# MAIN.net
KiCad netlist of a schematic drawn in Altium Designer
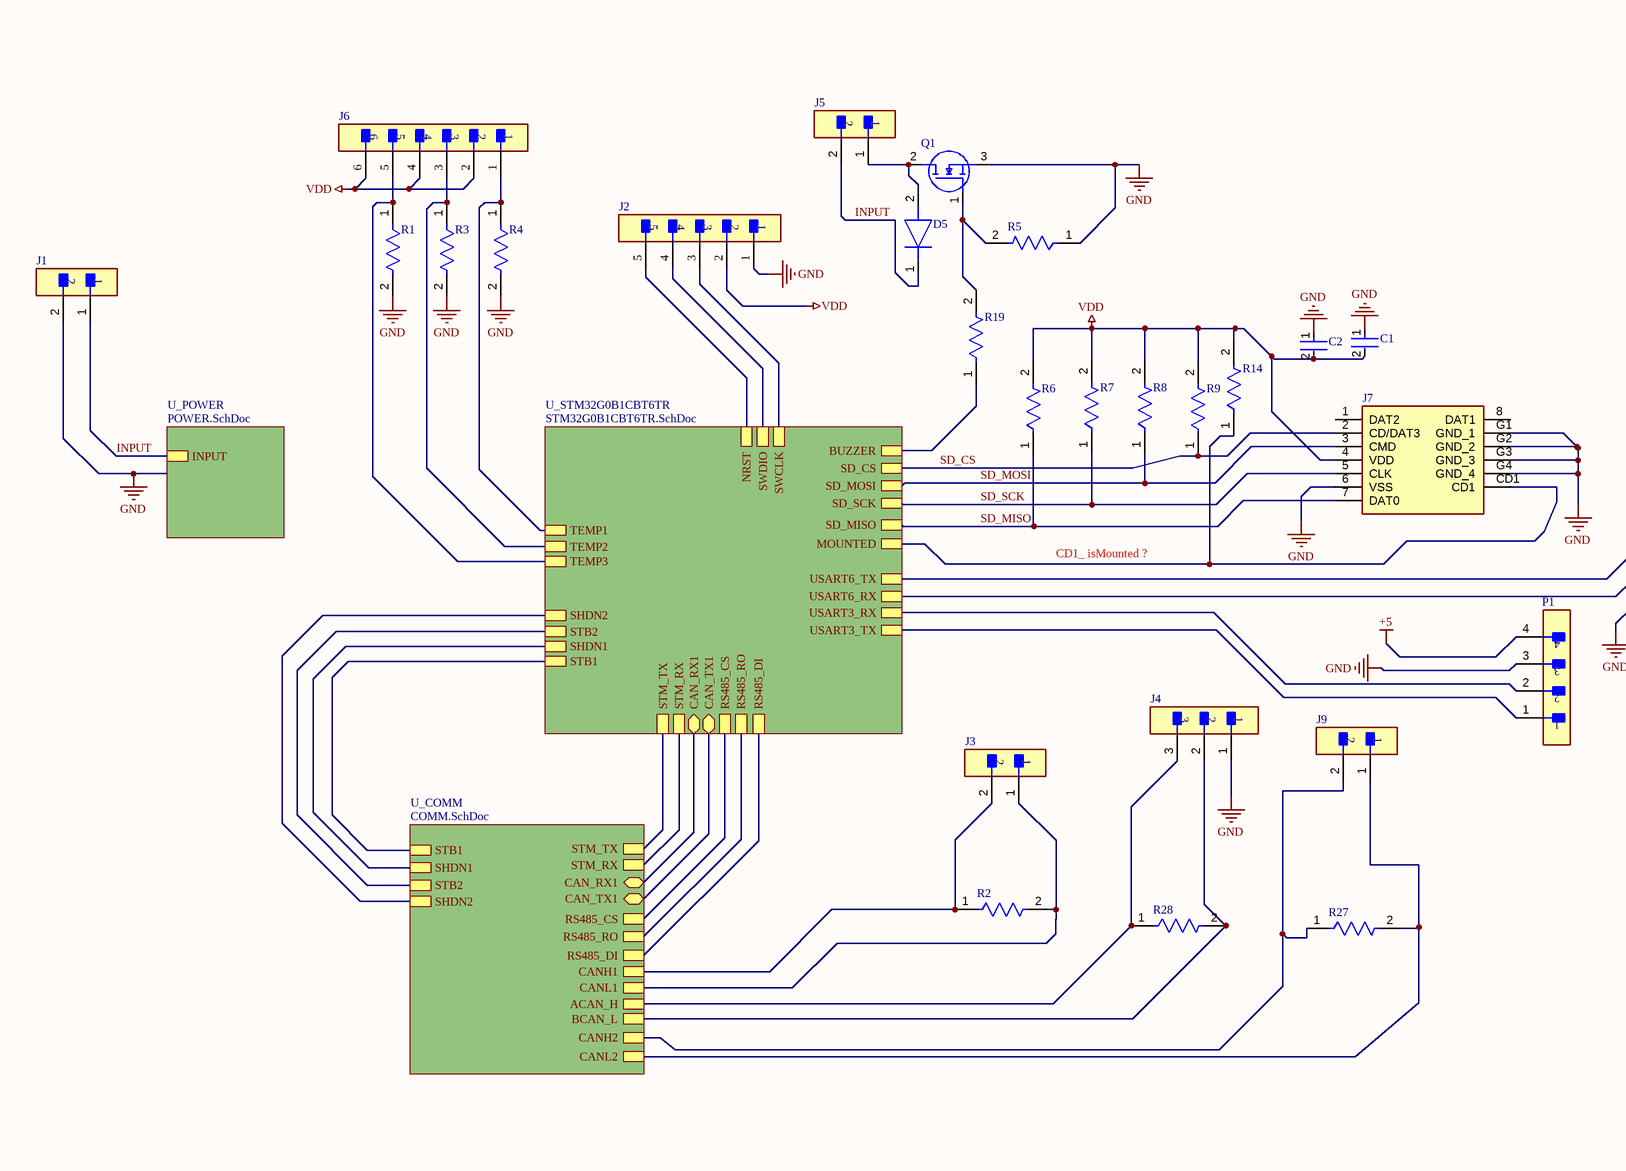
[diagram p0: MAIN.SchDoc, left]
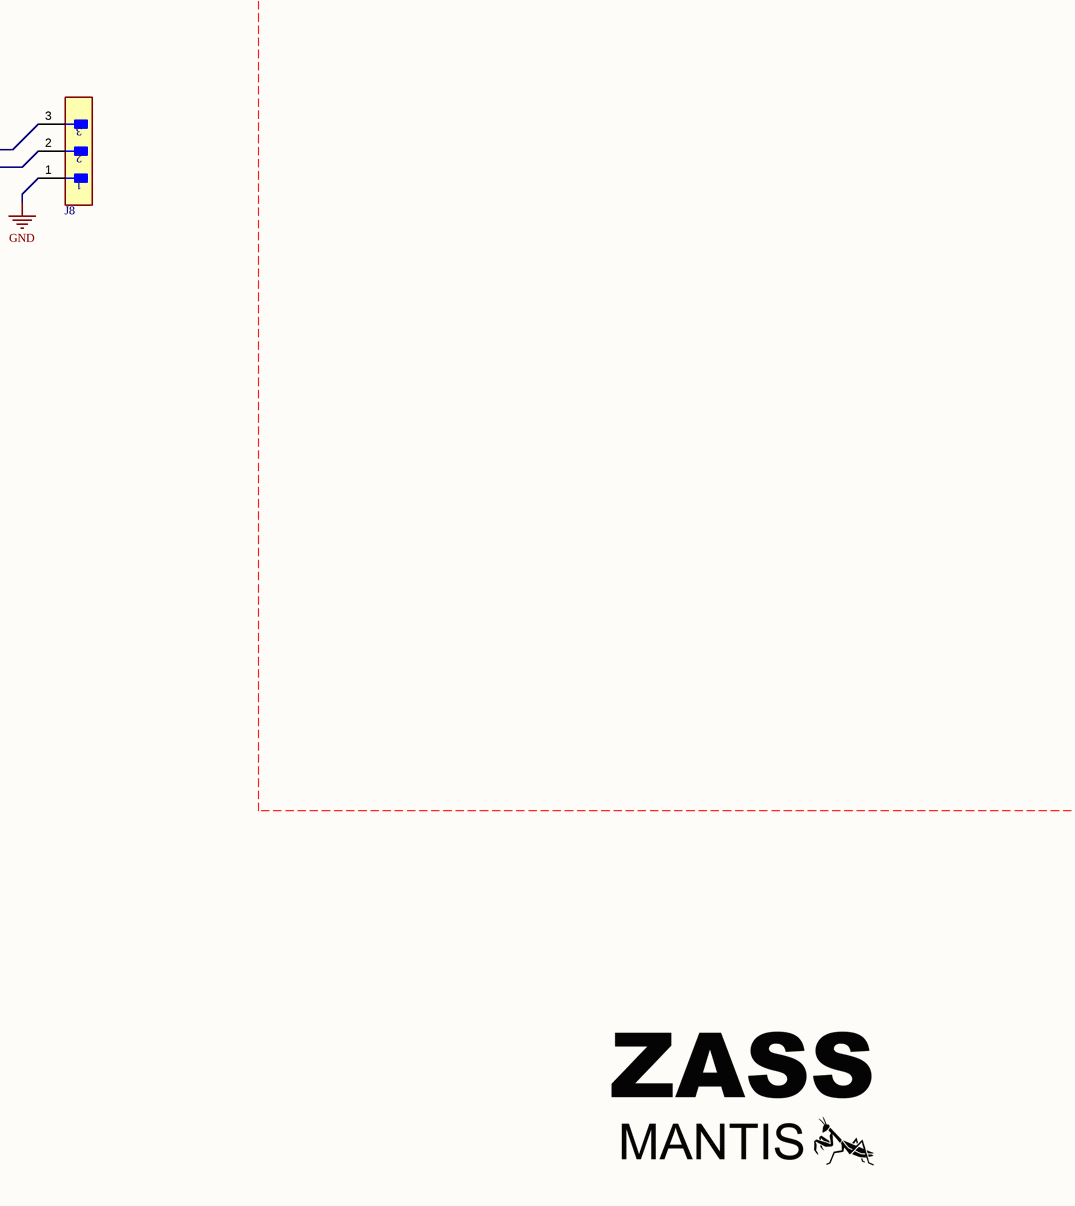
[diagram p1: MAIN.SchDoc, right]

(export (version "E")
  (design (tool "Eeschema 10.0.6"))
  (components
    (comp (ref "C1")
      (value "CC0805KRX7R5BB104")
      (footprint "FP-CC0805-EA-MFG")
      (description "CAP CER X7R 0805")
      (libsource (lib "Altium Content Vault") (part "b4654b650e69147ec39a6b967a45e02"))
    )
    (comp (ref "C2")
      (value "CC0805KRX7R5BB104")
      (footprint "FP-CC0805-EA-MFG")
      (description "CAP CER X7R 0805")
      (libsource (lib "Altium Content Vault") (part "b4654b650e69147ec39a6b967a45e02"))
    )
    (comp (ref "D5")
      (value "1N4007WS")
      (footprint "SamacSys:SOD2613X110N")
      (description "Diode")
      (libsource (lib "*") (part "1N4007WS"))
    )
    (comp (ref "J1")
      (value "B2B-XH-A(LF)(SN)")
      (footprint "FP-B2B-XH-A_LF_SN-MFG")
      (description "CONN HEADER VERT 2POS 2.5MM")
      (libsource (lib "Altium Content Vault") (part "3bc925449376181038e59eaffc5286c"))
    )
    (comp (ref "J2")
      (value "B5B-XH-AM(LF)(SN)")
      (footprint "FP-B5B-XH-AM_LF_SN-MFG")
      (description "CONN HEADER VERT 5POS 2.5MM")
      (libsource (lib "Altium Content Vault") (part "bf93c07fd2649a848d0ec8585582aab"))
    )
    (comp (ref "J3")
      (value "B2B-XH-A(LF)(SN)")
      (footprint "FP-B2B-XH-A_LF_SN-MFG")
      (description "CONN HEADER VERT 2POS 2.5MM")
      (libsource (lib "Altium Content Vault") (part "3bc925449376181038e59eaffc5286c"))
    )
    (comp (ref "J4")
      (value "B3B-XH-A(LF)(SN)")
      (footprint "FP-B3B-XH-A_LF_SN-MFG")
      (description "CONN HEADER VERT 3POS 2.5MM")
      (libsource (lib "") (part "0d3f023dd272f625e17a2be33dea85f_1"))
    )
    (comp (ref "J5")
      (value "S2B-XH-A(LF)(SN)")
      (footprint "FP-B2B-XH-A_LF_SN-MFG")
      (description "CONN HEADER VERT 2POS 2.5MM")
      (libsource (lib "Altium Content Vault") (part "3bc925449376181038e59eaffc5286c"))
    )
    (comp (ref "J6")
      (value "B6B-XH-AM(LF)(SN)")
      (footprint "FP-B6B-XH-AM_LF_SN-MFG")
      (description "CONN HEADER VERT 6POS 2.5MM")
      (libsource (lib "Altium Content Vault") (part "f2cb566baf1c37ab5a3b8e90bbeafd6"))
    )
    (comp (ref "J7")
      (value "MSD-4-A")
      (footprint "SamacSys:MSD4A")
      (description "Connector")
      (fields (field (name "MOUSER PART NUMBER") "179-MSD-4-A"))
      (libsource (lib "*") (part "MSD-4-A"))
    )
    (comp (ref "J8")
      (value "B3B-XH-A(LF)(SN)")
      (footprint "FP-B3B-XH-A_LF_SN-MFG")
      (description "CONN HEADER VERT 3POS 2.5MM")
      (libsource (lib "Altium Content Vault") (part "0d3f023dd272f625e17a2be33dea85f"))
    )
    (comp (ref "J9")
      (value "B2B-XH-A(LF)(SN)")
      (footprint "FP-B2B-XH-A_LF_SN-MFG")
      (description "CONN HEADER VERT 2POS 2.5MM")
      (libsource (lib "Altium Content Vault") (part "3bc925449376181038e59eaffc5286c"))
    )
    (comp (ref "P1")
      (value "B4B-XH-A(LF)(SN)")
      (footprint "FP-B4B-XH-A_LF_SN-MFG")
      (description "CONN HEADER VERT 4POS 2.5MM")
      (libsource (lib "Altium Content Vault") (part "299a8cea1bdcbc3624fe62c390fa72c"))
    )
    (comp (ref "Q1")
      (value "AO3422")
      (footprint "SamacSys:SOT95P237X112-3N")
      (description "MOSFET (N-Channel)")
      (libsource (lib "*") (part "AO3422"))
    )
    (comp (ref "R1")
      (value "CRGCQ0603J10K")
      (footprint "FP-CRGCQ0603-IPC_C")
      (description "CRGCQ 0603 10K 5%")
      (fields
        (field (name "TOLERANCE") "0.05")
        (field (name "OCTOPART") "https://octopart.com/crgcq0603j10k-te+connectivity-91018097")
      )
      (libsource (lib "Altium Content Vault") (part "1029c3af85768c4190bb7ad29bc67b5"))
    )
    (comp (ref "R2")
      (value "CRGCQ0603F120R")
      (footprint "FP-CRGCQ0603-IPC_C")
      (description "CRGCQ0603 120Ω 1% ±100ppm/°C 75V")
      (fields
        (field (name "TOLERANCE") "0.01")
        (field (name "OCTOPART") "https://octopart.com/crgcq0603f120r-te+connectivity-91018039")
      )
      (libsource (lib "Altium Content Vault") (part "1029c3af85768c4190bb7ad29bc67b5"))
    )
    (comp (ref "R3")
      (value "CRGCQ0603J10K")
      (footprint "FP-CRGCQ0603-IPC_C")
      (description "CRGCQ 0603 10K 5%")
      (fields
        (field (name "TOLERANCE") "0.05")
        (field (name "OCTOPART") "https://octopart.com/crgcq0603j10k-te+connectivity-91018097")
      )
      (libsource (lib "Altium Content Vault") (part "1029c3af85768c4190bb7ad29bc67b5"))
    )
    (comp (ref "R4")
      (value "CRGCQ0603J10K")
      (footprint "FP-CRGCQ0603-IPC_C")
      (description "CRGCQ 0603 10K 5%")
      (fields
        (field (name "TOLERANCE") "0.05")
        (field (name "OCTOPART") "https://octopart.com/crgcq0603j10k-te+connectivity-91018097")
      )
      (libsource (lib "Altium Content Vault") (part "1029c3af85768c4190bb7ad29bc67b5"))
    )
    (comp (ref "R5")
      (value "CRGCQ0603J10K")
      (footprint "FP-CRGCQ0603-IPC_C")
      (description "CRGCQ 0603 10K 5%")
      (fields
        (field (name "TOLERANCE") "0.05")
        (field (name "OCTOPART") "https://octopart.com/crgcq0603j10k-te+connectivity-91018097")
      )
      (libsource (lib "Altium Content Vault") (part "1029c3af85768c4190bb7ad29bc67b5"))
    )
    (comp (ref "R6")
      (value "CRCW06034K70FKEA")
      (footprint "FP-CRCW0603-e3-IPC_A")
      (description "RES Thick Film, 4.7kΩ, 1%, 0.1W, 100ppm/°C, 0603")
      (fields (field (name "TOLERANCE") "1%"))
      (libsource (lib "Altium Content Vault") (part "1029c3af85768c4190bb7ad29bc67b5"))
    )
    (comp (ref "R7")
      (value "CRCW06034K70FKEA")
      (footprint "FP-CRCW0603-e3-IPC_A")
      (description "RES Thick Film, 4.7kΩ, 1%, 0.1W, 100ppm/°C, 0603")
      (fields (field (name "TOLERANCE") "1%"))
      (libsource (lib "Altium Content Vault") (part "1029c3af85768c4190bb7ad29bc67b5"))
    )
    (comp (ref "R8")
      (value "CRCW06034K70FKEA")
      (footprint "FP-CRCW0603-e3-IPC_A")
      (description "RES Thick Film, 4.7kΩ, 1%, 0.1W, 100ppm/°C, 0603")
      (fields (field (name "TOLERANCE") "1%"))
      (libsource (lib "Altium Content Vault") (part "1029c3af85768c4190bb7ad29bc67b5"))
    )
    (comp (ref "R9")
      (value "CRCW06034K70FKEA")
      (footprint "FP-CRCW0603-e3-IPC_A")
      (description "RES Thick Film, 4.7kΩ, 1%, 0.1W, 100ppm/°C, 0603")
      (fields (field (name "TOLERANCE") "1%"))
      (libsource (lib "Altium Content Vault") (part "1029c3af85768c4190bb7ad29bc67b5"))
    )
    (comp (ref "R14")
      (value "CRCW06034K70FKEA")
      (footprint "FP-CRCW0603-e3-IPC_A")
      (description "RES Thick Film, 4.7kΩ, 1%, 0.1W, 100ppm/°C, 0603")
      (fields (field (name "TOLERANCE") "1%"))
      (libsource (lib "Altium Content Vault") (part "1029c3af85768c4190bb7ad29bc67b5"))
    )
    (comp (ref "R19")
      (value "CRGCQ0603F1K2")
      (footprint "FP-CRGCQ0603-IPC_C")
      (description "CRGCQ 0603 1K2 1%")
      (fields
        (field (name "OCTOPART") "https://octopart.com/crgcq0603f1k2-te+connectivity-91018051")
        (field (name "MANUFACTURER") "TE Connectivity")
      )
      (libsource (lib "Altium Content Vault") (part "1029c3af85768c4190bb7ad29bc67b5"))
    )
    (comp (ref "R27")
      (value "CRGCQ0603F120R")
      (footprint "FP-CRGCQ0603-IPC_C")
      (description "CRGCQ0603 120Ω 1% ±100ppm/°C 75V")
      (fields
        (field (name "TOLERANCE") "0.01")
        (field (name "OCTOPART") "https://octopart.com/crgcq0603f120r-te+connectivity-91018039")
      )
      (libsource (lib "Altium Content Vault") (part "1029c3af85768c4190bb7ad29bc67b5"))
    )
    (comp (ref "R28")
      (value "CRGCQ0603F120R")
      (footprint "FP-CRGCQ0603-IPC_C")
      (description "CRGCQ0603 120Ω 1% ±100ppm/°C 75V")
      (fields
        (field (name "TOLERANCE") "0.01")
        (field (name "OCTOPART") "https://octopart.com/crgcq0603f120r-te+connectivity-91018039")
      )
      (libsource (lib "Altium Content Vault") (part "1029c3af85768c4190bb7ad29bc67b5"))
    )
  )
  (nets
    (net (code "1") (name "+5") (class "Default")
      (node (ref "P1") (pin "4") (pinfunction "4_4") (pintype "passive"))
    )
    (net (code "2") (name "/ACAN_H") (class "Default")
      (node (ref "J4") (pin "3") (pinfunction "3_3") (pintype "passive"))
      (node (ref "R28") (pin "1") (pinfunction "1_1") (pintype "passive"))
    )
    (net (code "3") (name "/BCAN_L") (class "Default")
      (node (ref "J4") (pin "2") (pinfunction "2_2") (pintype "passive"))
      (node (ref "R28") (pin "2") (pinfunction "2_2") (pintype "passive"))
    )
    (net (code "4") (name "/BUZZER") (class "Default")
      (node (ref "R19") (pin "1") (pinfunction "1_1") (pintype "passive"))
    )
    (net (code "5") (name "/CANH1") (class "Default")
      (node (ref "J3") (pin "2") (pinfunction "2_2") (pintype "passive"))
      (node (ref "R2") (pin "1") (pinfunction "1_1") (pintype "passive"))
    )
    (net (code "6") (name "/CANH2") (class "Default")
      (node (ref "J9") (pin "2") (pinfunction "2_2") (pintype "passive"))
      (node (ref "R27") (pin "1") (pinfunction "1_1") (pintype "passive"))
    )
    (net (code "7") (name "/CANL1") (class "Default")
      (node (ref "J3") (pin "1") (pinfunction "1_1") (pintype "passive"))
      (node (ref "R2") (pin "2") (pinfunction "2_2") (pintype "passive"))
    )
    (net (code "8") (name "/CANL2") (class "Default")
      (node (ref "J9") (pin "1") (pinfunction "1_1") (pintype "passive"))
      (node (ref "R27") (pin "2") (pinfunction "2_2") (pintype "passive"))
    )
    (net (code "11") (name "/INPUT") (class "Default")
      (node (ref "D5") (pin "1") (pinfunction "K_1") (pintype "passive"))
      (node (ref "J1") (pin "1") (pinfunction "1_1") (pintype "passive"))
      (node (ref "J5") (pin "2") (pinfunction "2_2") (pintype "passive"))
    )
    (net (code "12") (name "/MOUNTED") (class "Default")
      (node (ref "J7") (pin "CD1") (pinfunction "CD1_CD1") (pintype "passive"))
      (node (ref "R14") (pin "1") (pinfunction "1_1") (pintype "passive"))
    )
    (net (code "13") (name "/NRST") (class "Default")
      (node (ref "J2") (pin "5") (pinfunction "5_5") (pintype "passive"))
    )
    (net (code "17") (name "/SD_CS") (class "Default")
      (node (ref "J7") (pin "2") (pinfunction "CD/DAT3_2") (pintype "passive"))
      (node (ref "R9") (pin "1") (pinfunction "1_1") (pintype "passive"))
    )
    (net (code "18") (name "/SD_MISO") (class "Default")
      (node (ref "J7") (pin "7") (pinfunction "DAT0_7") (pintype "passive"))
      (node (ref "R6") (pin "1") (pinfunction "1_1") (pintype "passive"))
    )
    (net (code "19") (name "/SD_MOSI") (class "Default")
      (node (ref "J7") (pin "3") (pinfunction "CMD_3") (pintype "passive"))
      (node (ref "R8") (pin "1") (pinfunction "1_1") (pintype "passive"))
    )
    (net (code "20") (name "/SD_SCK") (class "Default")
      (node (ref "J7") (pin "5") (pinfunction "CLK_5") (pintype "passive"))
      (node (ref "R7") (pin "1") (pinfunction "1_1") (pintype "passive"))
    )
    (net (code "27") (name "/SWCLK") (class "Default")
      (node (ref "J2") (pin "3") (pinfunction "3_3") (pintype "passive"))
    )
    (net (code "28") (name "/SWDIO") (class "Default")
      (node (ref "J2") (pin "4") (pinfunction "4_4") (pintype "passive"))
    )
    (net (code "29") (name "/TEMP1") (class "Default")
      (node (ref "J6") (pin "1") (pinfunction "1_1") (pintype "passive"))
      (node (ref "R4") (pin "1") (pinfunction "1_1") (pintype "passive"))
    )
    (net (code "30") (name "/TEMP2") (class "Default")
      (node (ref "J6") (pin "3") (pinfunction "3_3") (pintype "passive"))
      (node (ref "R3") (pin "1") (pinfunction "1_1") (pintype "passive"))
    )
    (net (code "31") (name "/TEMP3") (class "Default")
      (node (ref "J6") (pin "5") (pinfunction "5_5") (pintype "passive"))
      (node (ref "R1") (pin "1") (pinfunction "1_1") (pintype "passive"))
    )
    (net (code "32") (name "/USART3_RX") (class "Default")
      (node (ref "P1") (pin "2") (pinfunction "2_2") (pintype "passive"))
    )
    (net (code "33") (name "/USART3_TX") (class "Default")
      (node (ref "P1") (pin "1") (pinfunction "1_1") (pintype "passive"))
    )
    (net (code "34") (name "/USART6_RX") (class "Default")
      (node (ref "J8") (pin "2") (pinfunction "2_2") (pintype "passive"))
    )
    (net (code "35") (name "/USART6_TX") (class "Default")
      (node (ref "J8") (pin "3") (pinfunction "3_3") (pintype "passive"))
    )
    (net (code "36") (name "GND") (class "Default")
      (node (ref "C1") (pin "1") (pinfunction "1_1") (pintype "passive"))
      (node (ref "C2") (pin "1") (pinfunction "1_1") (pintype "passive"))
      (node (ref "J1") (pin "2") (pinfunction "2_2") (pintype "passive"))
      (node (ref "J2") (pin "1") (pinfunction "1_1") (pintype "passive"))
      (node (ref "J4") (pin "1") (pinfunction "1_1") (pintype "passive"))
      (node (ref "J7") (pin "6") (pinfunction "VSS_6") (pintype "passive"))
      (node (ref "J7") (pin "G1") (pinfunction "GND_1_G1") (pintype "passive"))
      (node (ref "J7") (pin "G2") (pinfunction "GND_2_G2") (pintype "passive"))
      (node (ref "J7") (pin "G3") (pinfunction "GND_3_G3") (pintype "passive"))
      (node (ref "J7") (pin "G4") (pinfunction "GND_4_G4") (pintype "passive"))
      (node (ref "J8") (pin "1") (pinfunction "1_1") (pintype "passive"))
      (node (ref "P1") (pin "3") (pinfunction "3_3") (pintype "passive"))
      (node (ref "Q1") (pin "3") (pinfunction "S_3") (pintype "passive"))
      (node (ref "R1") (pin "2") (pinfunction "2_2") (pintype "passive"))
      (node (ref "R3") (pin "2") (pinfunction "2_2") (pintype "passive"))
      (node (ref "R4") (pin "2") (pinfunction "2_2") (pintype "passive"))
      (node (ref "R5") (pin "1") (pinfunction "1_1") (pintype "passive"))
    )
    (net (code "37") (name "Net-(D5-A)") (class "Default")
      (node (ref "D5") (pin "2") (pinfunction "A_2") (pintype "passive"))
      (node (ref "J5") (pin "1") (pinfunction "1_1") (pintype "passive"))
      (node (ref "Q1") (pin "2") (pinfunction "D_2") (pintype "passive"))
    )
    (net (code "38") (name "Net-(Q1-G)") (class "Default")
      (node (ref "Q1") (pin "1") (pinfunction "G_1") (pintype "passive"))
      (node (ref "R19") (pin "2") (pinfunction "2_2") (pintype "passive"))
      (node (ref "R5") (pin "2") (pinfunction "2_2") (pintype "passive"))
    )
    (net (code "39") (name "VDD") (class "Default")
      (node (ref "C1") (pin "2") (pinfunction "2_2") (pintype "passive"))
      (node (ref "C2") (pin "2") (pinfunction "2_2") (pintype "passive"))
      (node (ref "J2") (pin "2") (pinfunction "2_2") (pintype "passive"))
      (node (ref "J6") (pin "2") (pinfunction "2_2") (pintype "passive"))
      (node (ref "J6") (pin "4") (pinfunction "4_4") (pintype "passive"))
      (node (ref "J6") (pin "6") (pinfunction "6_6") (pintype "passive"))
      (node (ref "J7") (pin "4") (pinfunction "VDD_4") (pintype "passive"))
      (node (ref "R14") (pin "2") (pinfunction "2_2") (pintype "passive"))
      (node (ref "R6") (pin "2") (pinfunction "2_2") (pintype "passive"))
      (node (ref "R7") (pin "2") (pinfunction "2_2") (pintype "passive"))
      (node (ref "R8") (pin "2") (pinfunction "2_2") (pintype "passive"))
      (node (ref "R9") (pin "2") (pinfunction "2_2") (pintype "passive"))
    )
    (net (code "40") (name "unconnected-(J7-DAT1-Pad8)") (class "Default")
      (node (ref "J7") (pin "8") (pinfunction "DAT1_8") (pintype "passive"))
    )
    (net (code "41") (name "unconnected-(J7-DAT2-Pad1)") (class "Default")
      (node (ref "J7") (pin "1") (pinfunction "DAT2_1") (pintype "passive"))
    )
  )
)
